# JETSON_RAW_PWR_FILTER.net
KiCad netlist of a schematic drawn in Altium Designer
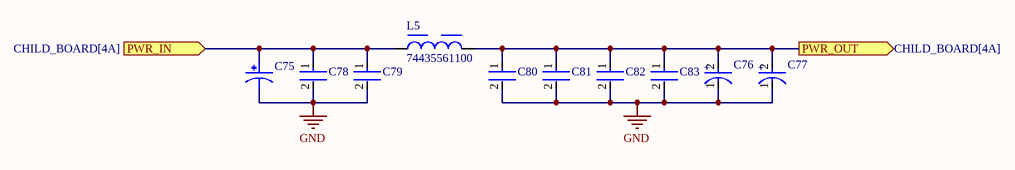
[diagram p0: JETSON_RAW_PWR_FILTER.SchDoc]

(export (version "E")
  (design (tool "Eeschema 10.0.6"))
  (components
    (comp (ref "C75")
      (value "MAL215099913E3")
      (footprint "MAL215099913E3-Footprint-1")
      (libsource (lib "Space Concordia") (part "MAL215099913E3"))
    )
    (comp (ref "C76")
      (value "T491X107K025AT")
      (footprint "FP-T491X107K025AT-MFG")
      (description "CAP TANT 100UF 10% 25V 2917")
      (fields (field (name "TOLERANCE") "10%") (field (name "VOLTAGE") "25V"))
      (libsource (lib "Altium Content Vault") (part "cf48714ba7e38822c1575c7ec0b6d1f"))
    )
    (comp (ref "C77")
      (value "T491X107K025AT")
      (footprint "FP-T491X107K025AT-MFG")
      (description "CAP TANT 100UF 10% 25V 2917")
      (fields (field (name "TOLERANCE") "10%") (field (name "VOLTAGE") "25V"))
      (libsource (lib "Altium Content Vault") (part "cf48714ba7e38822c1575c7ec0b6d1f"))
    )
    (comp (ref "C78")
      (value "CGA9P3X7S2A156M250KB")
      (footprint "FP-CGA9P-IPC_B")
      (description "Cap Ceramic 15uF 100V X7S 20% Pad SMD 2220 +125°C Automotive T/R")
      (fields (field (name "TOLERANCE") "20%"))
      (libsource (lib "Altium Content Vault") (part "b4654b650e69147ec39a6b967a45e02"))
    )
    (comp (ref "C79")
      (value "CGA9P3X7S2A156M250KB")
      (footprint "FP-CGA9P-IPC_B")
      (description "Cap Ceramic 15uF 100V X7S 20% Pad SMD 2220 +125°C Automotive T/R")
      (fields (field (name "TOLERANCE") "20%"))
      (libsource (lib "Altium Content Vault") (part "b4654b650e69147ec39a6b967a45e02"))
    )
    (comp (ref "C80")
      (value "12103D106KAT2A")
      (footprint "FP-1210-L_3_3_0_4-W_2_5_0-MFG")
      (description "General Purpose Ceramic Capacitor, 1210, 10uF, 10%, X5R, 15%, 25V")
      (fields (field (name "VOLTAGE") "25V") (field (name "TOLERANCE") "10%"))
      (libsource (lib "Altium Content Vault") (part "b4654b650e69147ec39a6b967a45e02"))
    )
    (comp (ref "C81")
      (value "12103D106KAT2A")
      (footprint "FP-1210-L_3_3_0_4-W_2_5_0-MFG")
      (description "General Purpose Ceramic Capacitor, 1210, 10uF, 10%, X5R, 15%, 25V")
      (fields (field (name "VOLTAGE") "25V") (field (name "TOLERANCE") "10%"))
      (libsource (lib "Altium Content Vault") (part "b4654b650e69147ec39a6b967a45e02"))
    )
    (comp (ref "C82")
      (value "12103D106KAT2A")
      (footprint "FP-1210-L_3_3_0_4-W_2_5_0-MFG")
      (description "General Purpose Ceramic Capacitor, 1210, 10uF, 10%, X5R, 15%, 25V")
      (fields (field (name "VOLTAGE") "25V") (field (name "TOLERANCE") "10%"))
      (libsource (lib "Altium Content Vault") (part "b4654b650e69147ec39a6b967a45e02"))
    )
    (comp (ref "C83")
      (value "12103D106KAT2A")
      (footprint "FP-1210-L_3_3_0_4-W_2_5_0-MFG")
      (description "General Purpose Ceramic Capacitor, 1210, 10uF, 10%, X5R, 15%, 25V")
      (fields (field (name "VOLTAGE") "25V") (field (name "TOLERANCE") "10%"))
      (libsource (lib "Altium Content Vault") (part "b4654b650e69147ec39a6b967a45e02"))
    )
    (comp (ref "L5")
      (value "74435561100")
      (footprint "WE-HCI_1890")
      (libsource (lib "Altium Content Vault") (part "Inductor - 3"))
    )
  )
  (nets
    (net (code "1") (name "/PWR_IN") (class "Default")
      (node (ref "C75") (pin "1") (pinfunction "1_1") (pintype "passive"))
      (node (ref "C78") (pin "1") (pinfunction "1_1") (pintype "passive"))
      (node (ref "C79") (pin "1") (pinfunction "1_1") (pintype "passive"))
      (node (ref "L5") (pin "1") (pinfunction "1_1") (pintype "passive"))
    )
    (net (code "2") (name "/PWR_OUT") (class "Default")
      (node (ref "C76") (pin "2") (pinfunction "A_2") (pintype "passive"))
      (node (ref "C77") (pin "2") (pinfunction "A_2") (pintype "passive"))
      (node (ref "C80") (pin "1") (pinfunction "1_1") (pintype "passive"))
      (node (ref "C81") (pin "1") (pinfunction "1_1") (pintype "passive"))
      (node (ref "C82") (pin "1") (pinfunction "1_1") (pintype "passive"))
      (node (ref "C83") (pin "1") (pinfunction "1_1") (pintype "passive"))
      (node (ref "L5") (pin "2") (pinfunction "2_2") (pintype "passive"))
    )
    (net (code "3") (name "GND") (class "Default")
      (node (ref "C75") (pin "2") (pinfunction "2_2") (pintype "passive"))
      (node (ref "C76") (pin "1") (pinfunction "C_1") (pintype "passive"))
      (node (ref "C77") (pin "1") (pinfunction "C_1") (pintype "passive"))
      (node (ref "C78") (pin "2") (pinfunction "2_2") (pintype "passive"))
      (node (ref "C79") (pin "2") (pinfunction "2_2") (pintype "passive"))
      (node (ref "C80") (pin "2") (pinfunction "2_2") (pintype "passive"))
      (node (ref "C81") (pin "2") (pinfunction "2_2") (pintype "passive"))
      (node (ref "C82") (pin "2") (pinfunction "2_2") (pintype "passive"))
      (node (ref "C83") (pin "2") (pinfunction "2_2") (pintype "passive"))
    )
  )
)
